# test.net
KiCad netlist of a schematic drawn in EasyEDA
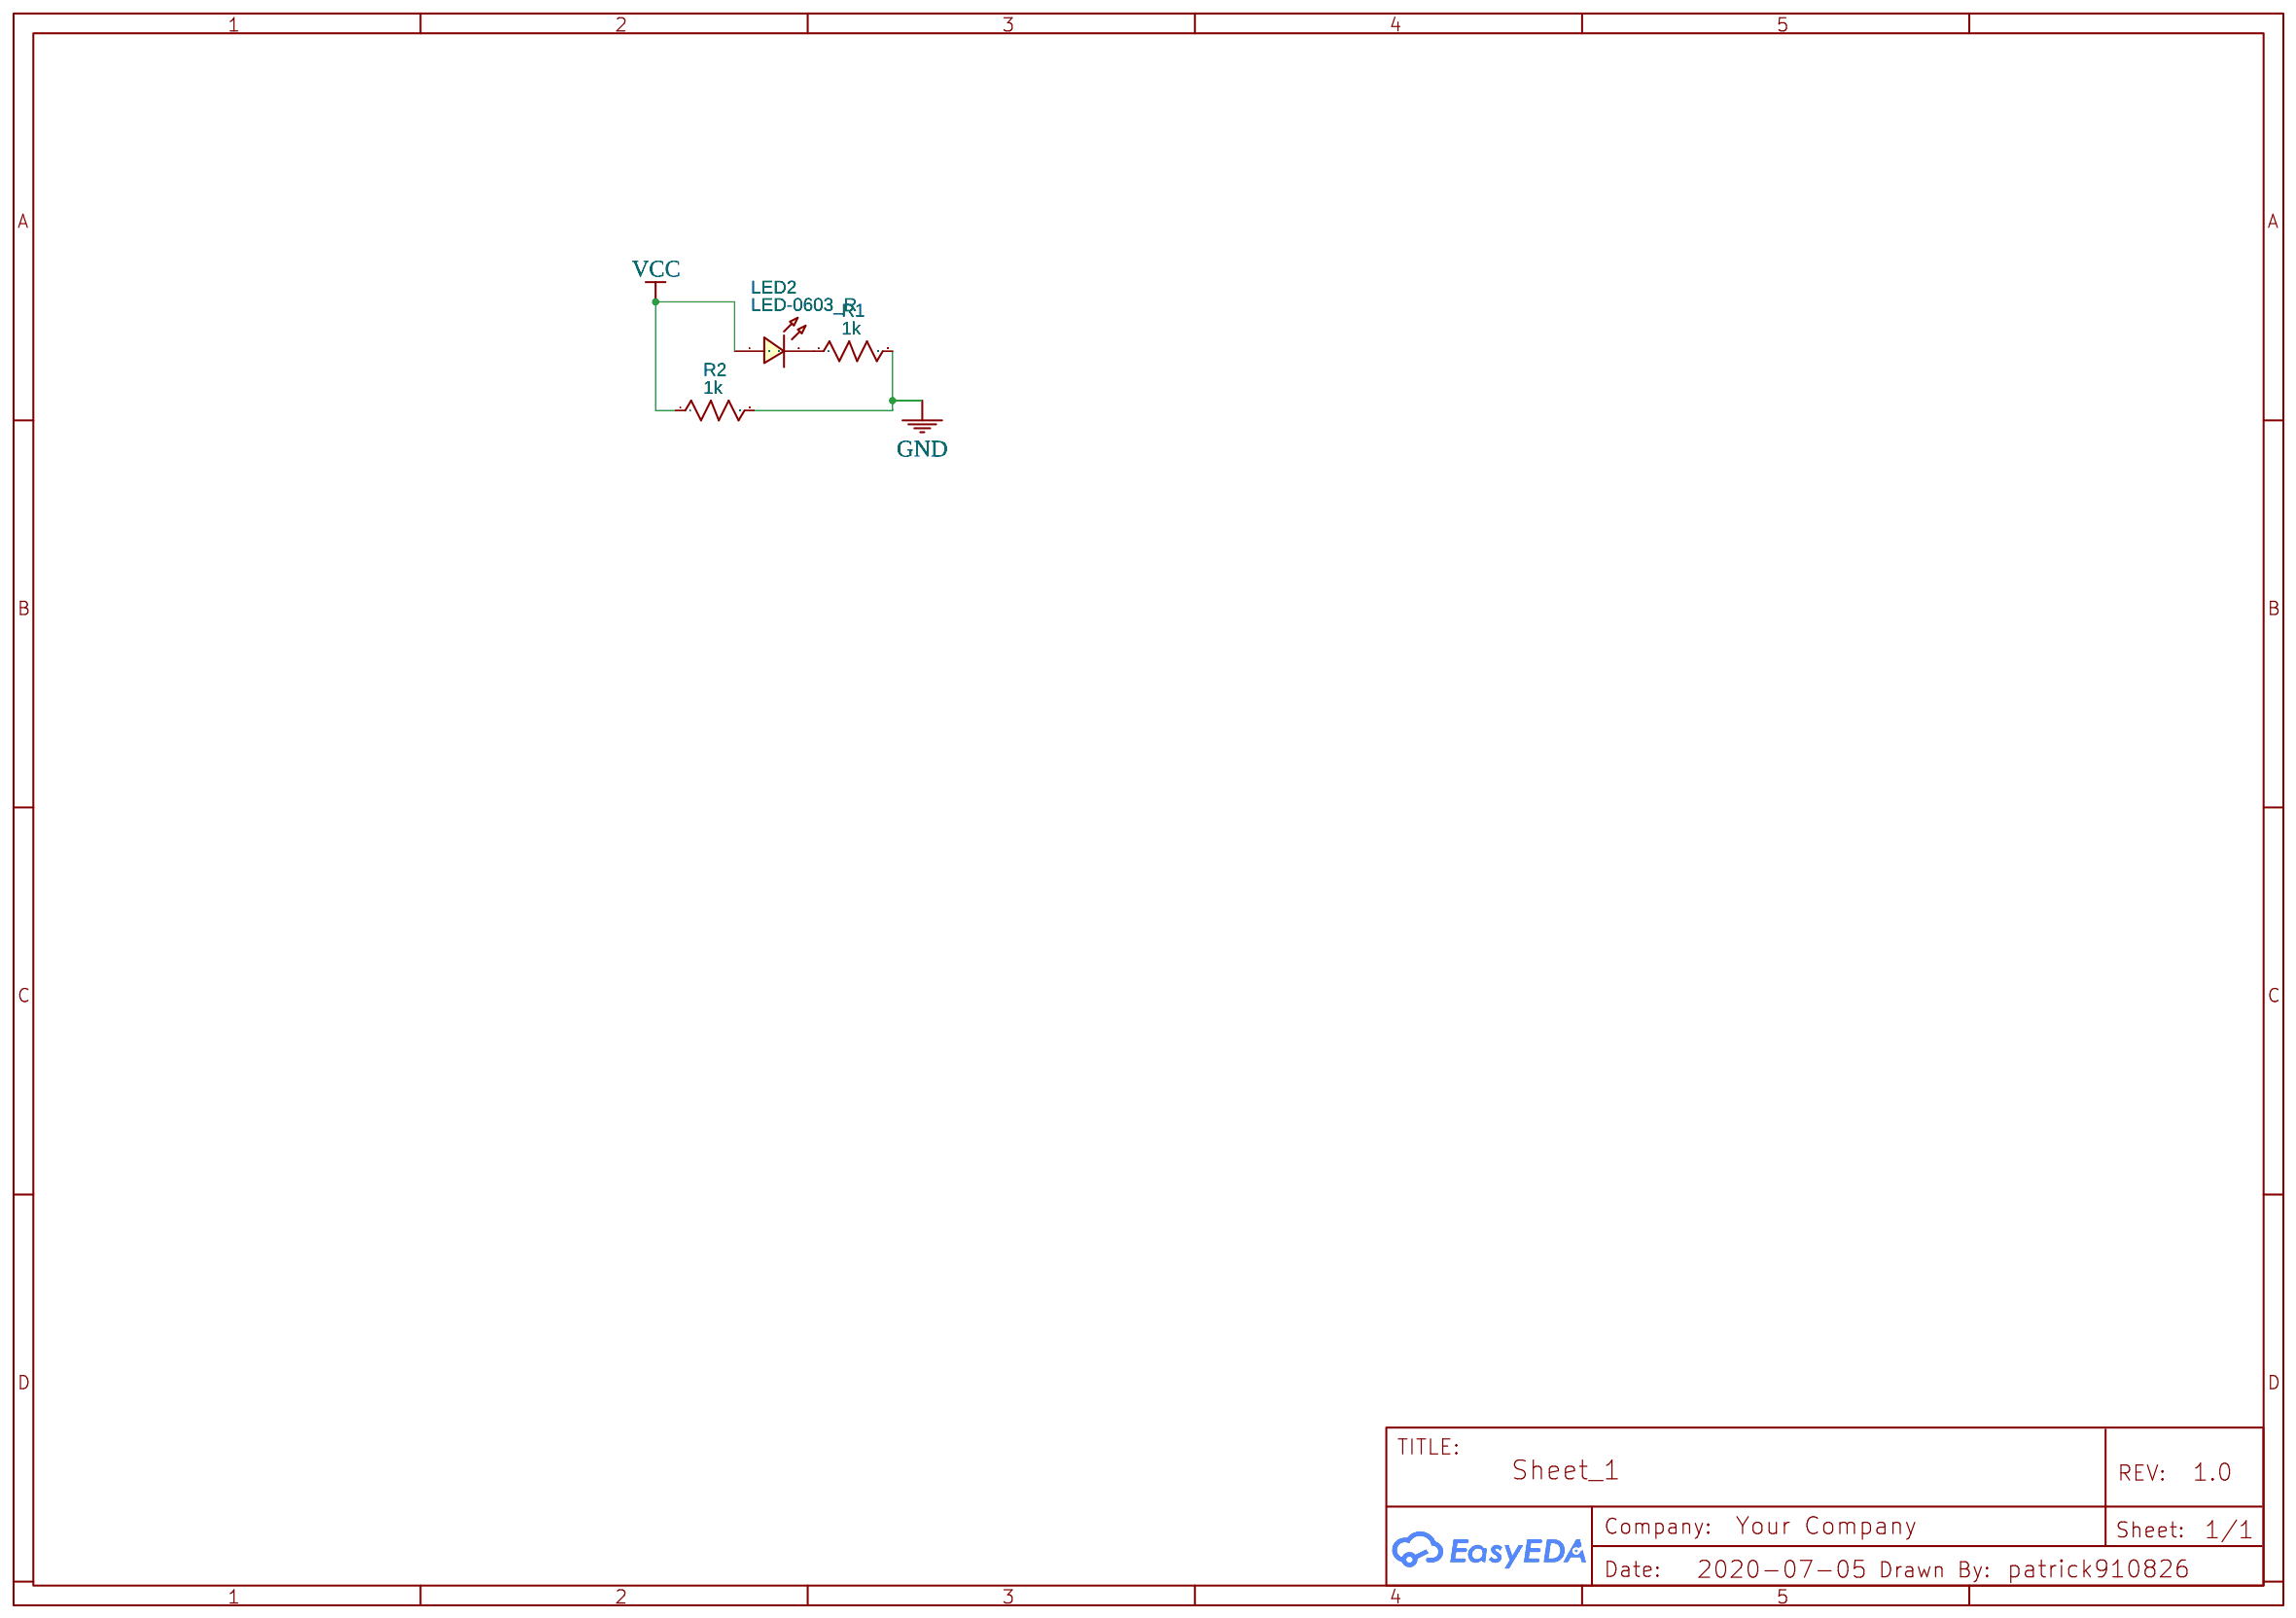
[diagram p0: schematic sheet]

(export (version "E")
  (design (tool "Eeschema 10.0.6"))
  (components
    (comp (ref "LED2")
      (value "LED-0603_R")
      (fields
        (field (name "BOM_Manufacturer Part") "19-217/R6C-AL1M2VY/3T")
        (field (name "BOM_Supplier Part") "C72044")
      )
      (libsource (lib "") (part "LED-0603_R"))
    )
    (comp (ref "R1") (value "1k") (libsource (lib "") (part "R_AXIAL-0.5_US")))
    (comp (ref "R2") (value "1k") (libsource (lib "") (part "R_AXIAL-0.5_US")))
  )
  (nets
    (net (code "1") (name "GND") (class "Default")
      (node (ref "R1") (pin "2") (pinfunction "2_2") (pintype "unspecified"))
      (node (ref "R2") (pin "2") (pinfunction "2_2") (pintype "unspecified"))
    )
    (net (code "2") (name "Net-(LED2-Pad2)") (class "Default")
      (node (ref "LED2") (pin "2") (pinfunction "2_2") (pintype "unspecified"))
      (node (ref "R1") (pin "1") (pinfunction "1_1") (pintype "unspecified"))
    )
    (net (code "3") (name "VCC") (class "Default")
      (node (ref "LED2") (pin "1") (pinfunction "1_1") (pintype "unspecified"))
      (node (ref "R2") (pin "1") (pinfunction "1_1") (pintype "unspecified"))
    )
  )
)
